# arduino_uno_pcb__with_lcd.net
KiCad netlist of a schematic drawn in EAGLE
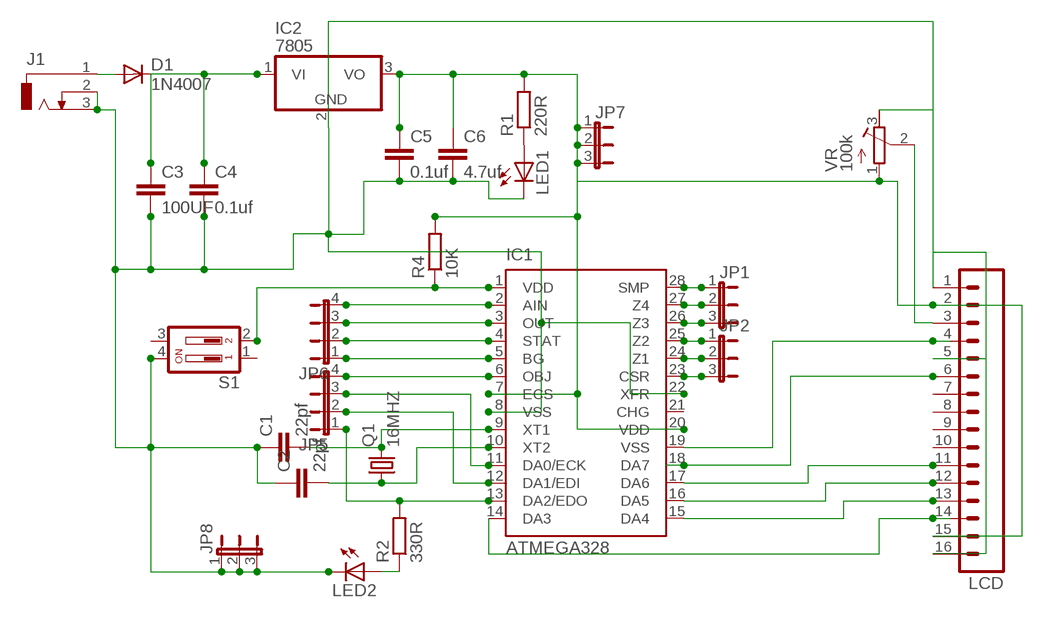
[diagram p0: schematic, sheet 1]

(export (version "E")
  (design (tool "Eeschema 10.0.6"))
  (components
    (comp (ref "C1")
      (value "22pf")
      (footprint "eagle-import:C2.5-2")
      (libsource (lib "eagle-import") (part "C2.5/2"))
    )
    (comp (ref "C2")
      (value "22pf")
      (footprint "eagle-import:C2.5-2")
      (libsource (lib "eagle-import") (part "C2.5/2"))
    )
    (comp (ref "C3")
      (value "100UF")
      (footprint "eagle-import:C2.5-2")
      (libsource (lib "eagle-import") (part "C2.5/2"))
    )
    (comp (ref "C4")
      (value "0.1uf")
      (footprint "eagle-import:C2.5-2")
      (libsource (lib "eagle-import") (part "C2.5/2"))
    )
    (comp (ref "C5")
      (value "0.1uf")
      (footprint "eagle-import:C2.5-2")
      (libsource (lib "eagle-import") (part "C2.5/2"))
    )
    (comp (ref "C6")
      (value "4.7uf")
      (footprint "eagle-import:C2.5-2")
      (libsource (lib "eagle-import") (part "C2.5/2"))
    )
    (comp (ref "D1")
      (value "1N4007")
      (footprint "eagle-import:DO41-10")
      (libsource (lib "eagle-import") (part "1N4004"))
    )
    (comp (ref "IC1")
      (value "ATMEGA328")
      (footprint "eagle-import:DIL28-3")
      (libsource (lib "eagle-import") (part "QT9701BD"))
    )
    (comp (ref "IC2")
      (value "7805")
      (footprint "eagle-import:TO220V")
      (libsource (lib "eagle-import") (part "78TV6"))
    )
    (comp (ref "J1")
      (value "DCJ0303")
      (footprint "eagle-import:DCJ0303")
      (libsource (lib "eagle-import") (part "DCJ0303"))
    )
    (comp (ref "JP1")
      (value "JP2E")
      (footprint "eagle-import:JP2")
      (libsource (lib "eagle-import") (part "JP2E"))
    )
    (comp (ref "JP2")
      (value "JP2E")
      (footprint "eagle-import:JP2")
      (libsource (lib "eagle-import") (part "JP2E"))
    )
    (comp (ref "JP5")
      (value "JP4E")
      (footprint "eagle-import:JP4")
      (libsource (lib "eagle-import") (part "JP4E"))
    )
    (comp (ref "JP6")
      (value "JP4E")
      (footprint "eagle-import:JP4")
      (libsource (lib "eagle-import") (part "JP4E"))
    )
    (comp (ref "JP7")
      (value "JP2E")
      (footprint "eagle-import:JP2")
      (libsource (lib "eagle-import") (part "JP2E"))
    )
    (comp (ref "JP8")
      (value "JP2E")
      (footprint "eagle-import:JP2")
      (libsource (lib "eagle-import") (part "JP2E"))
    )
    (comp (ref "LCD")
      (value "M16")
      (footprint "eagle-import:16P")
      (libsource (lib "eagle-import") (part "M16"))
    )
    (comp (ref "LED1")
      (value "LED3MM")
      (footprint "eagle-import:LED3MM")
      (libsource (lib "eagle-import") (part "LED3MM"))
    )
    (comp (ref "LED2")
      (value "LED3MM")
      (footprint "eagle-import:LED3MM")
      (libsource (lib "eagle-import") (part "LED3MM"))
    )
    (comp (ref "Q1")
      (value "16MHZ")
      (footprint "eagle-import:HC49_S")
      (libsource (lib "eagle-import") (part "CRYSTALHC49S"))
    )
    (comp (ref "R1")
      (value "220R")
      (footprint "eagle-import:0207_10")
      (libsource (lib "eagle-import") (part "R-EU_0207/10"))
    )
    (comp (ref "R2")
      (value "330R")
      (footprint "eagle-import:0207_10")
      (libsource (lib "eagle-import") (part "R-EU_0207/10"))
    )
    (comp (ref "R4")
      (value "10K")
      (footprint "eagle-import:0207_10")
      (libsource (lib "eagle-import") (part "R-EU_0207/10"))
    )
    (comp (ref "S1")
      (value "DP02")
      (footprint "eagle-import:DP-02")
      (fields (field (name "MPN") "MCDP02"))
      (libsource (lib "eagle-import") (part "DP02"))
    )
    (comp (ref "VR")
      (value "100k")
      (footprint "eagle-import:RTRIM64P")
      (libsource (lib "eagle-import") (part "R-TRIMM64P"))
    )
  )
  (nets
    (net (code "1") (name "Net-(D1-PadA)") (class "Default")
      (node (ref "D1") (pin "A") (pinfunction "A_A") (pintype "passive"))
      (node (ref "J1") (pin "1") (pinfunction "1_1") (pintype "passive"))
    )
    (net (code "2") (name "Net-(IC1-AIN)") (class "Default")
      (node (ref "IC1") (pin "2") (pinfunction "AIN_2") (pintype "input"))
      (node (ref "JP6") (pin "4") (pinfunction "4_4") (pintype "passive"))
    )
    (net (code "3") (name "Net-(IC1-BG)") (class "Default")
      (node (ref "IC1") (pin "5") (pinfunction "BG_5") (pintype "input"))
      (node (ref "JP6") (pin "1") (pinfunction "1_1") (pintype "passive"))
    )
    (net (code "4") (name "Net-(IC1-CSR)") (class "Default")
      (node (ref "IC1") (pin "23") (pinfunction "CSR_23") (pintype "output"))
      (node (ref "JP2") (pin "3") (pinfunction "3_3") (pintype "passive"))
    )
    (net (code "5") (name "Net-(IC1-DA0{slash}ECK)") (class "Default")
      (node (ref "IC1") (pin "11") (pinfunction "DA0/ECK_11") (pintype "output"))
      (node (ref "JP5") (pin "3") (pinfunction "3_3") (pintype "passive"))
    )
    (net (code "6") (name "Net-(IC1-DA1{slash}EDI)") (class "Default")
      (node (ref "IC1") (pin "12") (pinfunction "DA1/EDI_12") (pintype "output"))
      (node (ref "JP5") (pin "2") (pinfunction "2_2") (pintype "passive"))
    )
    (net (code "7") (name "Net-(IC1-DA2{slash}EDO)") (class "Default")
      (node (ref "IC1") (pin "13") (pinfunction "DA2/EDO_13") (pintype "output"))
      (node (ref "JP5") (pin "1") (pinfunction "1_1") (pintype "passive"))
      (node (ref "R2") (pin "2") (pinfunction "2_2") (pintype "passive"))
    )
    (net (code "8") (name "Net-(IC1-DA3)") (class "Default")
      (node (ref "IC1") (pin "14") (pinfunction "DA3_14") (pintype "output"))
      (node (ref "LCD") (pin "14") (pinfunction "14_14") (pintype "passive"))
    )
    (net (code "9") (name "Net-(IC1-DA4)") (class "Default")
      (node (ref "IC1") (pin "15") (pinfunction "DA4_15") (pintype "output"))
      (node (ref "LCD") (pin "13") (pinfunction "13_13") (pintype "passive"))
    )
    (net (code "10") (name "Net-(IC1-DA5)") (class "Default")
      (node (ref "IC1") (pin "16") (pinfunction "DA5_16") (pintype "output"))
      (node (ref "LCD") (pin "12") (pinfunction "12_12") (pintype "passive"))
    )
    (net (code "11") (name "Net-(IC1-DA6)") (class "Default")
      (node (ref "IC1") (pin "17") (pinfunction "DA6_17") (pintype "output"))
      (node (ref "LCD") (pin "11") (pinfunction "11_11") (pintype "passive"))
    )
    (net (code "12") (name "Net-(IC1-DA7)") (class "Default")
      (node (ref "IC1") (pin "18") (pinfunction "DA7_18") (pintype "output"))
      (node (ref "LCD") (pin "6") (pinfunction "6_6") (pintype "passive"))
    )
    (net (code "13") (name "Net-(IC1-ECS)") (class "Default")
      (node (ref "C5") (pin "1") (pinfunction "1_1") (pintype "passive"))
      (node (ref "C6") (pin "1") (pinfunction "1_1") (pintype "passive"))
      (node (ref "IC1") (pin "20") (pinfunction "VDD_20") (pintype "input"))
      (node (ref "IC1") (pin "7") (pinfunction "ECS_7") (pintype "output"))
      (node (ref "IC2") (pin "3") (pinfunction "VO_3") (pintype "passive"))
      (node (ref "JP7") (pin "1") (pinfunction "1_1") (pintype "passive"))
      (node (ref "JP7") (pin "2") (pinfunction "2_2") (pintype "passive"))
      (node (ref "JP7") (pin "3") (pinfunction "3_3") (pintype "passive"))
      (node (ref "LCD") (pin "15") (pinfunction "15_15") (pintype "passive"))
      (node (ref "LCD") (pin "2") (pinfunction "2_2") (pintype "passive"))
      (node (ref "R1") (pin "2") (pinfunction "2_2") (pintype "passive"))
      (node (ref "R4") (pin "2") (pinfunction "2_2") (pintype "passive"))
      (node (ref "VR") (pin "1") (pinfunction "E_1") (pintype "passive"))
    )
    (net (code "14") (name "Net-(IC1-OBJ)") (class "Default")
      (node (ref "IC1") (pin "6") (pinfunction "OBJ_6") (pintype "input"))
      (node (ref "JP5") (pin "4") (pinfunction "4_4") (pintype "passive"))
    )
    (net (code "15") (name "Net-(IC1-OUT)") (class "Default")
      (node (ref "IC1") (pin "3") (pinfunction "OUT_3") (pintype "output"))
      (node (ref "JP6") (pin "3") (pinfunction "3_3") (pintype "passive"))
    )
    (net (code "16") (name "Net-(IC1-SMP)") (class "Default")
      (node (ref "IC1") (pin "28") (pinfunction "SMP_28") (pintype "output"))
      (node (ref "JP1") (pin "1") (pinfunction "1_1") (pintype "passive"))
    )
    (net (code "17") (name "Net-(IC1-STAT)") (class "Default")
      (node (ref "IC1") (pin "4") (pinfunction "STAT_4") (pintype "output"))
      (node (ref "JP6") (pin "2") (pinfunction "2_2") (pintype "passive"))
    )
    (net (code "18") (name "Net-(IC1-VDD-Pad1)") (class "Default")
      (node (ref "IC1") (pin "1") (pinfunction "VDD_1") (pintype "input"))
      (node (ref "R4") (pin "1") (pinfunction "1_1") (pintype "passive"))
      (node (ref "S1") (pin "2") (pinfunction "2_2") (pintype "passive"))
    )
    (net (code "19") (name "Net-(IC1-VSS-Pad19)") (class "Default")
      (node (ref "IC1") (pin "19") (pinfunction "VSS_19") (pintype "input"))
      (node (ref "LCD") (pin "4") (pinfunction "4_4") (pintype "passive"))
    )
    (net (code "20") (name "Net-(IC1-XFR)") (class "Default")
      (node (ref "C1") (pin "1") (pinfunction "1_1") (pintype "passive"))
      (node (ref "C2") (pin "1") (pinfunction "1_1") (pintype "passive"))
      (node (ref "C3") (pin "2") (pinfunction "2_2") (pintype "passive"))
      (node (ref "C4") (pin "2") (pinfunction "2_2") (pintype "passive"))
      (node (ref "C5") (pin "2") (pinfunction "2_2") (pintype "passive"))
      (node (ref "C6") (pin "2") (pinfunction "2_2") (pintype "passive"))
      (node (ref "IC1") (pin "22") (pinfunction "XFR_22") (pintype "output"))
      (node (ref "IC1") (pin "8") (pinfunction "VSS_8") (pintype "input"))
      (node (ref "IC2") (pin "2") (pinfunction "GND_2") (pintype "passive"))
      (node (ref "J1") (pin "2") (pinfunction "2_2") (pintype "passive"))
      (node (ref "J1") (pin "3") (pinfunction "3_3") (pintype "passive"))
      (node (ref "JP8") (pin "1") (pinfunction "1_1") (pintype "passive"))
      (node (ref "JP8") (pin "2") (pinfunction "2_2") (pintype "passive"))
      (node (ref "JP8") (pin "3") (pinfunction "3_3") (pintype "passive"))
      (node (ref "LCD") (pin "1") (pinfunction "1_1") (pintype "passive"))
      (node (ref "LCD") (pin "16") (pinfunction "16_16") (pintype "passive"))
      (node (ref "LCD") (pin "5") (pinfunction "5_5") (pintype "passive"))
      (node (ref "LED1") (pin "K") (pinfunction "C_K") (pintype "passive"))
      (node (ref "LED2") (pin "K") (pinfunction "C_K") (pintype "passive"))
      (node (ref "S1") (pin "4") (pinfunction "4_4") (pintype "passive"))
      (node (ref "VR") (pin "3") (pinfunction "A_3") (pintype "passive"))
    )
    (net (code "21") (name "Net-(IC1-XT1)") (class "Default")
      (node (ref "C1") (pin "2") (pinfunction "2_2") (pintype "passive"))
      (node (ref "IC1") (pin "9") (pinfunction "XT1_9") (pintype "input"))
      (node (ref "Q1") (pin "2") (pinfunction "2_2") (pintype "passive"))
    )
    (net (code "22") (name "Net-(IC1-XT2)") (class "Default")
      (node (ref "C2") (pin "2") (pinfunction "2_2") (pintype "passive"))
      (node (ref "IC1") (pin "10") (pinfunction "XT2_10") (pintype "output"))
      (node (ref "Q1") (pin "1") (pinfunction "1_1") (pintype "passive"))
    )
    (net (code "23") (name "Net-(IC1-Z1)") (class "Default")
      (node (ref "IC1") (pin "24") (pinfunction "Z1_24") (pintype "output"))
      (node (ref "JP2") (pin "2") (pinfunction "2_2") (pintype "passive"))
    )
    (net (code "24") (name "Net-(IC1-Z2)") (class "Default")
      (node (ref "IC1") (pin "25") (pinfunction "Z2_25") (pintype "output"))
      (node (ref "JP2") (pin "1") (pinfunction "1_1") (pintype "passive"))
    )
    (net (code "25") (name "Net-(IC1-Z3)") (class "Default")
      (node (ref "IC1") (pin "26") (pinfunction "Z3_26") (pintype "output"))
      (node (ref "JP1") (pin "3") (pinfunction "3_3") (pintype "passive"))
    )
    (net (code "26") (name "Net-(IC1-Z4)") (class "Default")
      (node (ref "IC1") (pin "27") (pinfunction "Z4_27") (pintype "output"))
      (node (ref "JP1") (pin "2") (pinfunction "2_2") (pintype "passive"))
    )
    (net (code "27") (name "Net-(IC2-VI)") (class "Default")
      (node (ref "C3") (pin "1") (pinfunction "1_1") (pintype "passive"))
      (node (ref "C4") (pin "1") (pinfunction "1_1") (pintype "passive"))
      (node (ref "D1") (pin "C") (pinfunction "C_C") (pintype "passive"))
      (node (ref "IC2") (pin "1") (pinfunction "VI_1") (pintype "input"))
    )
    (net (code "28") (name "Net-(LED1-PadA)") (class "Default")
      (node (ref "LED1") (pin "A") (pinfunction "A_A") (pintype "passive"))
      (node (ref "R1") (pin "1") (pinfunction "1_1") (pintype "passive"))
    )
    (net (code "29") (name "Net-(LED2-PadA)") (class "Default")
      (node (ref "LED2") (pin "A") (pinfunction "A_A") (pintype "passive"))
      (node (ref "R2") (pin "1") (pinfunction "1_1") (pintype "passive"))
    )
    (net (code "30") (name "Net-(VR-S)") (class "Default")
      (node (ref "LCD") (pin "3") (pinfunction "3_3") (pintype "passive"))
      (node (ref "VR") (pin "2") (pinfunction "S_2") (pintype "passive"))
    )
    (net (code "31") (name "unconnected-(IC1-CHG-Pad21)") (class "Default")
      (node (ref "IC1") (pin "21") (pinfunction "CHG_21") (pintype "output"))
    )
    (net (code "32") (name "unconnected-(LCD-Pad7)") (class "Default")
      (node (ref "LCD") (pin "7") (pinfunction "7_7") (pintype "passive"))
    )
    (net (code "33") (name "unconnected-(LCD-Pad8)") (class "Default")
      (node (ref "LCD") (pin "8") (pinfunction "8_8") (pintype "passive"))
    )
    (net (code "34") (name "unconnected-(LCD-Pad9)") (class "Default")
      (node (ref "LCD") (pin "9") (pinfunction "9_9") (pintype "passive"))
    )
    (net (code "35") (name "unconnected-(LCD-Pad10)") (class "Default")
      (node (ref "LCD") (pin "10") (pinfunction "10_10") (pintype "passive"))
    )
    (net (code "36") (name "unconnected-(S1-Pad1)") (class "Default")
      (node (ref "S1") (pin "1") (pinfunction "1_1") (pintype "passive"))
    )
    (net (code "37") (name "unconnected-(S1-Pad3)") (class "Default")
      (node (ref "S1") (pin "3") (pinfunction "3_3") (pintype "passive"))
    )
  )
)
